# Tayloe_Detector_v2.net
KiCad netlist of a schematic drawn in EAGLE
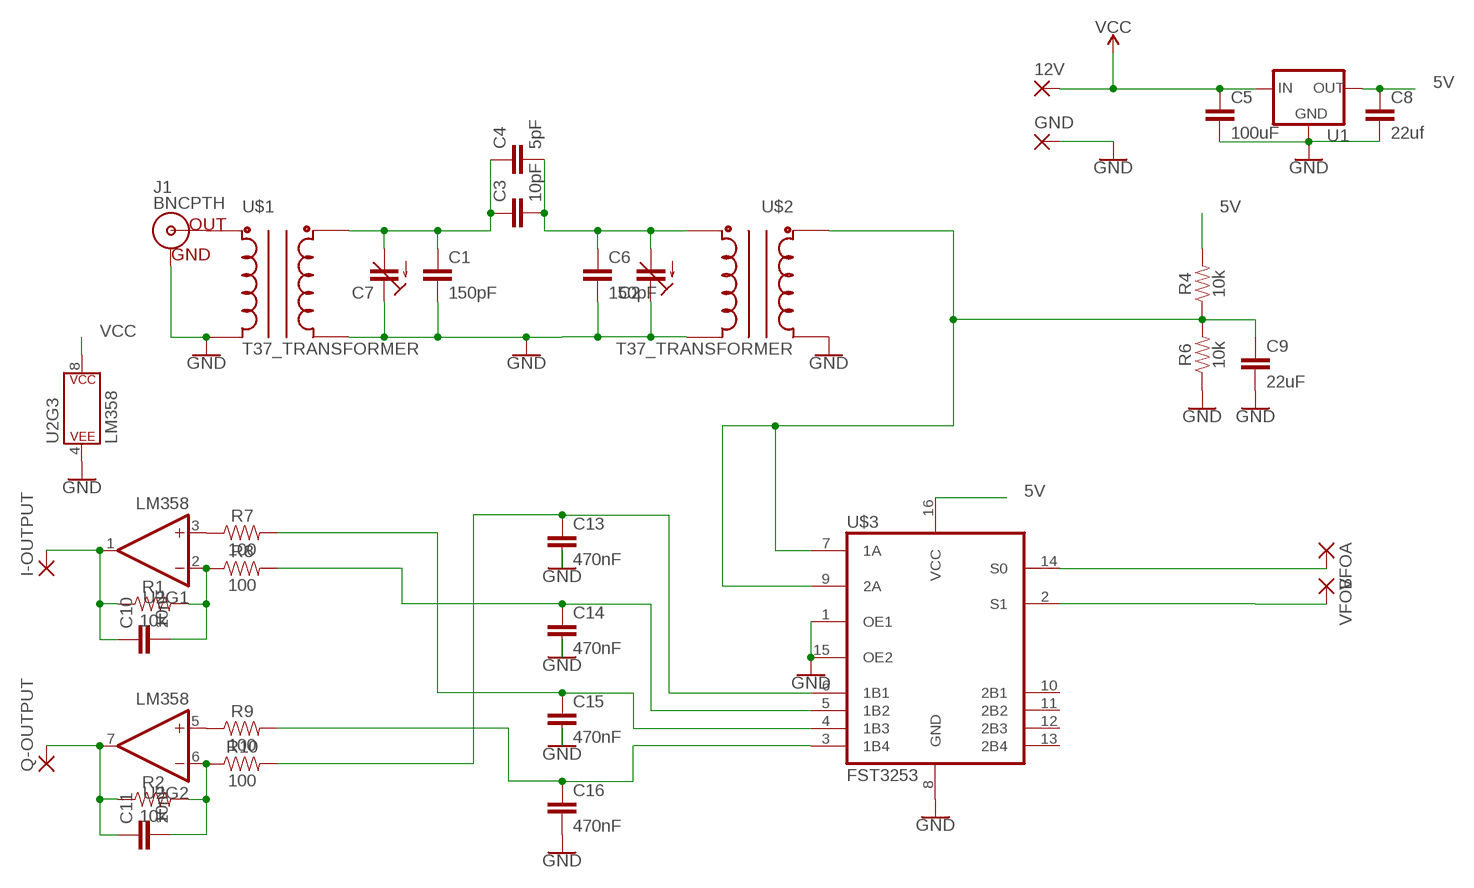
[diagram p0: schematic, sheet 1]

(export (version "E")
  (design (tool "Eeschema 10.0.6"))
  (components
    (comp (ref "12V")
      (value "3,17/1,1")
      (footprint "eagle-import:3,17_1,1")
      (libsource (lib "eagle-import") (part "3,17/1,1"))
    )
    (comp (ref "C1")
      (value "150pF")
      (footprint "eagle-import:C5B3.5")
      (libsource (lib "eagle-import") (part "C5/3.5"))
    )
    (comp (ref "C2")
      (value "C-TRIMMTZ03")
      (footprint "eagle-import:CTRIMTZ03")
      (libsource (lib "eagle-import") (part "C-TRIMMTZ03"))
    )
    (comp (ref "C3")
      (value "10pF")
      (footprint "eagle-import:C5B3.5")
      (libsource (lib "eagle-import") (part "C5/3.5"))
    )
    (comp (ref "C4")
      (value "5pF")
      (footprint "eagle-import:C5B3.5")
      (libsource (lib "eagle-import") (part "C5/3.5"))
    )
    (comp (ref "C5")
      (value "100uF")
      (footprint "eagle-import:C5B3.5")
      (libsource (lib "eagle-import") (part "C5/3.5"))
    )
    (comp (ref "C6")
      (value "150pF")
      (footprint "eagle-import:C5B3.5")
      (libsource (lib "eagle-import") (part "C5/3.5"))
    )
    (comp (ref "C7")
      (value "C-TRIMMTZ03")
      (footprint "eagle-import:CTRIMTZ03")
      (libsource (lib "eagle-import") (part "C-TRIMMTZ03"))
    )
    (comp (ref "C8")
      (value "22uf")
      (footprint "eagle-import:C5B3.5")
      (libsource (lib "eagle-import") (part "C5/3.5"))
    )
    (comp (ref "C9")
      (value "22uF")
      (footprint "eagle-import:C5B3.5")
      (libsource (lib "eagle-import") (part "C5/3.5"))
    )
    (comp (ref "C10")
      (value "10nF")
      (footprint "eagle-import:C5B3.5")
      (libsource (lib "eagle-import") (part "C5/3.5"))
    )
    (comp (ref "C11")
      (value "10nF")
      (footprint "eagle-import:C5B3.5")
      (libsource (lib "eagle-import") (part "C5/3.5"))
    )
    (comp (ref "C13")
      (value "470nF")
      (footprint "eagle-import:C5B3.5")
      (libsource (lib "eagle-import") (part "C5/3.5"))
    )
    (comp (ref "C14")
      (value "470nF")
      (footprint "eagle-import:C5B3.5")
      (libsource (lib "eagle-import") (part "C5/3.5"))
    )
    (comp (ref "C15")
      (value "470nF")
      (footprint "eagle-import:C5B3.5")
      (libsource (lib "eagle-import") (part "C5/3.5"))
    )
    (comp (ref "C16")
      (value "470nF")
      (footprint "eagle-import:C5B3.5")
      (libsource (lib "eagle-import") (part "C5/3.5"))
    )
    (comp (ref "GND")
      (value "3,17/1,1")
      (footprint "eagle-import:3,17_1,1")
      (libsource (lib "eagle-import") (part "3,17/1,1"))
    )
    (comp (ref "I-OUTPUT")
      (value "3,17/1,1")
      (footprint "eagle-import:3,17_1,1")
      (libsource (lib "eagle-import") (part "3,17/1,1"))
    )
    (comp (ref "J1")
      (value "BNCPTH")
      (footprint "eagle-import:BNC")
      (libsource (lib "eagle-import") (part "BNCPTH"))
    )
    (comp (ref "Q-OUTPUT")
      (value "3,17/1,1")
      (footprint "eagle-import:3,17_1,1")
      (libsource (lib "eagle-import") (part "3,17/1,1"))
    )
    (comp (ref "R1")
      (value "10k")
      (footprint "eagle-import:AXIAL-0.3")
      (libsource (lib "eagle-import") (part "1KOHM-HORIZ-1/4W-1%"))
    )
    (comp (ref "R2")
      (value "10k")
      (footprint "eagle-import:AXIAL-0.3")
      (libsource (lib "eagle-import") (part "1KOHM-HORIZ-1/4W-1%"))
    )
    (comp (ref "R4")
      (value "10k")
      (footprint "eagle-import:AXIAL-0.3")
      (libsource (lib "eagle-import") (part "1KOHM-HORIZ-1/4W-1%"))
    )
    (comp (ref "R6")
      (value "10k")
      (footprint "eagle-import:AXIAL-0.3")
      (libsource (lib "eagle-import") (part "1KOHM-HORIZ-1/4W-1%"))
    )
    (comp (ref "R7")
      (value "100")
      (footprint "eagle-import:AXIAL-0.3")
      (libsource (lib "eagle-import") (part "1KOHM-HORIZ-1/4W-1%"))
    )
    (comp (ref "R8")
      (value "100")
      (footprint "eagle-import:AXIAL-0.3")
      (libsource (lib "eagle-import") (part "1KOHM-HORIZ-1/4W-1%"))
    )
    (comp (ref "R9")
      (value "100")
      (footprint "eagle-import:AXIAL-0.3")
      (libsource (lib "eagle-import") (part "1KOHM-HORIZ-1/4W-1%"))
    )
    (comp (ref "R10")
      (value "100")
      (footprint "eagle-import:AXIAL-0.3")
      (libsource (lib "eagle-import") (part "1KOHM-HORIZ-1/4W-1%"))
    )
    (comp (ref "U$1")
      (value "T37_TRANSFORMER")
      (footprint "eagle-import:T37_TRANSFORMER")
      (libsource (lib "eagle-import") (part "T37_TRANSFORMER"))
    )
    (comp (ref "U$2")
      (value "T37_TRANSFORMER")
      (footprint "eagle-import:T37_TRANSFORMER")
      (libsource (lib "eagle-import") (part "T37_TRANSFORMER"))
    )
    (comp (ref "U$3")
      (value "FST3253")
      (footprint "eagle-import:SO16")
      (libsource (lib "eagle-import") (part "FST3253"))
    )
    (comp (ref "U1")
      (value "V_REG_78XXTO-92_UNTESTED")
      (footprint "eagle-import:TO-92")
      (libsource (lib "eagle-import") (part "V_REG_78XXTO-92_UNTESTED"))
    )
    (comp (ref "U2")
      (value "LM358")
      (footprint "eagle-import:DIP08")
      (libsource (lib "eagle-import") (part "LM358"))
    )
    (comp (ref "VFOA")
      (value "3,17/1,1")
      (footprint "eagle-import:3,17_1,1")
      (libsource (lib "eagle-import") (part "3,17/1,1"))
    )
    (comp (ref "VFOB")
      (value "3,17/1,1")
      (footprint "eagle-import:3,17_1,1")
      (libsource (lib "eagle-import") (part "3,17/1,1"))
    )
  )
  (nets
    (net (code "1") (name "/5V") (class "Default")
      (node (ref "C8") (pin "1") (pinfunction "1_1") (pintype "passive"))
      (node (ref "R4") (pin "P$2") (pinfunction "2_P$2") (pintype "passive"))
      (node (ref "U$3") (pin "16") (pinfunction "VCC_16") (pintype "bidirectional"))
      (node (ref "U1") (pin "1") (pinfunction "OUT_1") (pintype "passive"))
    )
    (net (code "2") (name "GND") (class "Default")
      (node (ref "C1") (pin "2") (pinfunction "2_2") (pintype "passive"))
      (node (ref "C13") (pin "2") (pinfunction "2_2") (pintype "passive"))
      (node (ref "C14") (pin "2") (pinfunction "2_2") (pintype "passive"))
      (node (ref "C15") (pin "2") (pinfunction "2_2") (pintype "passive"))
      (node (ref "C16") (pin "2") (pinfunction "2_2") (pintype "passive"))
      (node (ref "C2") (pin "1") (pinfunction "E_1") (pintype "passive"))
      (node (ref "C5") (pin "2") (pinfunction "2_2") (pintype "passive"))
      (node (ref "C6") (pin "2") (pinfunction "2_2") (pintype "passive"))
      (node (ref "C7") (pin "1") (pinfunction "E_1") (pintype "passive"))
      (node (ref "C8") (pin "2") (pinfunction "2_2") (pintype "passive"))
      (node (ref "C9") (pin "2") (pinfunction "2_2") (pintype "passive"))
      (node (ref "GND") (pin "1") (pinfunction "P_1") (pintype "passive"))
      (node (ref "J1") (pin "GND") (pinfunction "GND_GND") (pintype "bidirectional"))
      (node (ref "R6") (pin "P$1") (pinfunction "1_P$1") (pintype "passive"))
      (node (ref "U$1") (pin "C1A") (pinfunction "C1A_C1A") (pintype "bidirectional"))
      (node (ref "U$1") (pin "C2A") (pinfunction "C2A_C2A") (pintype "bidirectional"))
      (node (ref "U$2") (pin "C1A") (pinfunction "C1A_C1A") (pintype "bidirectional"))
      (node (ref "U$2") (pin "C2A") (pinfunction "C2A_C2A") (pintype "bidirectional"))
      (node (ref "U$3") (pin "1") (pinfunction "OE1_1") (pintype "bidirectional"))
      (node (ref "U$3") (pin "15") (pinfunction "OE2_15") (pintype "bidirectional"))
      (node (ref "U$3") (pin "8") (pinfunction "GND_8") (pintype "bidirectional"))
      (node (ref "U1") (pin "2") (pinfunction "GND_2") (pintype "input"))
      (node (ref "U2") (pin "4") (pinfunction "P$V-_4") (pintype "bidirectional"))
    )
    (net (code "3") (name "Net-(C2-A)") (class "Default")
      (node (ref "C2") (pin "2") (pinfunction "A_2") (pintype "passive"))
      (node (ref "C3") (pin "2") (pinfunction "2_2") (pintype "passive"))
      (node (ref "C4") (pin "2") (pinfunction "2_2") (pintype "passive"))
      (node (ref "C6") (pin "1") (pinfunction "1_1") (pintype "passive"))
      (node (ref "U$2") (pin "C2B") (pinfunction "C2B_C2B") (pintype "bidirectional"))
    )
    (net (code "4") (name "Net-(C7-A)") (class "Default")
      (node (ref "C1") (pin "1") (pinfunction "1_1") (pintype "passive"))
      (node (ref "C3") (pin "1") (pinfunction "1_1") (pintype "passive"))
      (node (ref "C4") (pin "1") (pinfunction "1_1") (pintype "passive"))
      (node (ref "C7") (pin "2") (pinfunction "A_2") (pintype "passive"))
      (node (ref "U$1") (pin "C2B") (pinfunction "C2B_C2B") (pintype "bidirectional"))
    )
    (net (code "5") (name "Net-(I-OUTPUT-P)") (class "Default")
      (node (ref "C10") (pin "1") (pinfunction "1_1") (pintype "passive"))
      (node (ref "I-OUTPUT") (pin "1") (pinfunction "P_1") (pintype "passive"))
      (node (ref "R1") (pin "P$1") (pinfunction "1_P$1") (pintype "passive"))
      (node (ref "U2") (pin "1") (pinfunction "OUT_1") (pintype "output"))
    )
    (net (code "6") (name "Net-(J1-OUT)") (class "Default")
      (node (ref "J1") (pin "S") (pinfunction "OUT_S") (pintype "bidirectional"))
      (node (ref "U$1") (pin "C1B") (pinfunction "C1B_C1B") (pintype "bidirectional"))
    )
    (net (code "7") (name "Net-(Q-OUTPUT-P)") (class "Default")
      (node (ref "C11") (pin "1") (pinfunction "1_1") (pintype "passive"))
      (node (ref "Q-OUTPUT") (pin "1") (pinfunction "P_1") (pintype "passive"))
      (node (ref "R2") (pin "P$1") (pinfunction "1_P$1") (pintype "passive"))
      (node (ref "U2") (pin "7") (pinfunction "OUT_7") (pintype "output"))
    )
    (net (code "8") (name "Net-(R1-2)") (class "Default")
      (node (ref "C10") (pin "2") (pinfunction "2_2") (pintype "passive"))
      (node (ref "R1") (pin "P$2") (pinfunction "2_P$2") (pintype "passive"))
      (node (ref "R8") (pin "P$1") (pinfunction "1_P$1") (pintype "passive"))
      (node (ref "U2") (pin "2") (pinfunction "-IN_2") (pintype "input"))
    )
    (net (code "9") (name "Net-(R4-1)") (class "Default")
      (node (ref "C9") (pin "1") (pinfunction "1_1") (pintype "passive"))
      (node (ref "R4") (pin "P$1") (pinfunction "1_P$1") (pintype "passive"))
      (node (ref "R6") (pin "P$2") (pinfunction "2_P$2") (pintype "passive"))
      (node (ref "U$2") (pin "C1B") (pinfunction "C1B_C1B") (pintype "bidirectional"))
      (node (ref "U$3") (pin "7") (pinfunction "1A_7") (pintype "bidirectional"))
      (node (ref "U$3") (pin "9") (pinfunction "2A_9") (pintype "bidirectional"))
    )
    (net (code "10") (name "Net-(R7-1)") (class "Default")
      (node (ref "R7") (pin "P$1") (pinfunction "1_P$1") (pintype "passive"))
      (node (ref "U2") (pin "3") (pinfunction "+IN_3") (pintype "input"))
    )
    (net (code "11") (name "Net-(R7-2)") (class "Default")
      (node (ref "C15") (pin "1") (pinfunction "1_1") (pintype "passive"))
      (node (ref "R7") (pin "P$2") (pinfunction "2_P$2") (pintype "passive"))
      (node (ref "U$3") (pin "4") (pinfunction "1B3_4") (pintype "output"))
    )
    (net (code "12") (name "Net-(R8-2)") (class "Default")
      (node (ref "C14") (pin "1") (pinfunction "1_1") (pintype "passive"))
      (node (ref "R8") (pin "P$2") (pinfunction "2_P$2") (pintype "passive"))
      (node (ref "U$3") (pin "5") (pinfunction "1B2_5") (pintype "input"))
    )
    (net (code "13") (name "Net-(R9-1)") (class "Default")
      (node (ref "R9") (pin "P$1") (pinfunction "1_P$1") (pintype "passive"))
      (node (ref "U2") (pin "5") (pinfunction "+IN_5") (pintype "input"))
    )
    (net (code "14") (name "Net-(R9-2)") (class "Default")
      (node (ref "C16") (pin "1") (pinfunction "1_1") (pintype "passive"))
      (node (ref "R9") (pin "P$2") (pinfunction "2_P$2") (pintype "passive"))
      (node (ref "U$3") (pin "3") (pinfunction "1B4_3") (pintype "output"))
    )
    (net (code "15") (name "Net-(R10-1)") (class "Default")
      (node (ref "C11") (pin "2") (pinfunction "2_2") (pintype "passive"))
      (node (ref "R10") (pin "P$1") (pinfunction "1_P$1") (pintype "passive"))
      (node (ref "R2") (pin "P$2") (pinfunction "2_P$2") (pintype "passive"))
      (node (ref "U2") (pin "6") (pinfunction "-IN_6") (pintype "input"))
    )
    (net (code "16") (name "Net-(R10-2)") (class "Default")
      (node (ref "C13") (pin "1") (pinfunction "1_1") (pintype "passive"))
      (node (ref "R10") (pin "P$2") (pinfunction "2_P$2") (pintype "passive"))
      (node (ref "U$3") (pin "6") (pinfunction "1B1_6") (pintype "input"))
    )
    (net (code "17") (name "Net-(U$3-S0)") (class "Default")
      (node (ref "U$3") (pin "14") (pinfunction "S0_14") (pintype "bidirectional"))
      (node (ref "VFOA") (pin "1") (pinfunction "P_1") (pintype "passive"))
    )
    (net (code "18") (name "Net-(U$3-S1)") (class "Default")
      (node (ref "U$3") (pin "2") (pinfunction "S1_2") (pintype "bidirectional"))
      (node (ref "VFOB") (pin "1") (pinfunction "P_1") (pintype "passive"))
    )
    (net (code "19") (name "VCC") (class "Default")
      (node (ref "12V") (pin "1") (pinfunction "P_1") (pintype "passive"))
      (node (ref "C5") (pin "1") (pinfunction "1_1") (pintype "passive"))
      (node (ref "U1") (pin "3") (pinfunction "IN_3") (pintype "input"))
      (node (ref "U2") (pin "8") (pinfunction "P$V+_8") (pintype "bidirectional"))
    )
    (net (code "20") (name "unconnected-(U$3-2B1-Pad10)") (class "Default")
      (node (ref "U$3") (pin "10") (pinfunction "2B1_10") (pintype "output"))
    )
    (net (code "21") (name "unconnected-(U$3-2B2-Pad11)") (class "Default")
      (node (ref "U$3") (pin "11") (pinfunction "2B2_11") (pintype "output"))
    )
    (net (code "22") (name "unconnected-(U$3-2B3-Pad12)") (class "Default")
      (node (ref "U$3") (pin "12") (pinfunction "2B3_12") (pintype "input"))
    )
    (net (code "23") (name "unconnected-(U$3-2B4-Pad13)") (class "Default")
      (node (ref "U$3") (pin "13") (pinfunction "2B4_13") (pintype "input"))
    )
  )
)
